# diodes.net
KiCad netlist of a schematic drawn in EAGLE
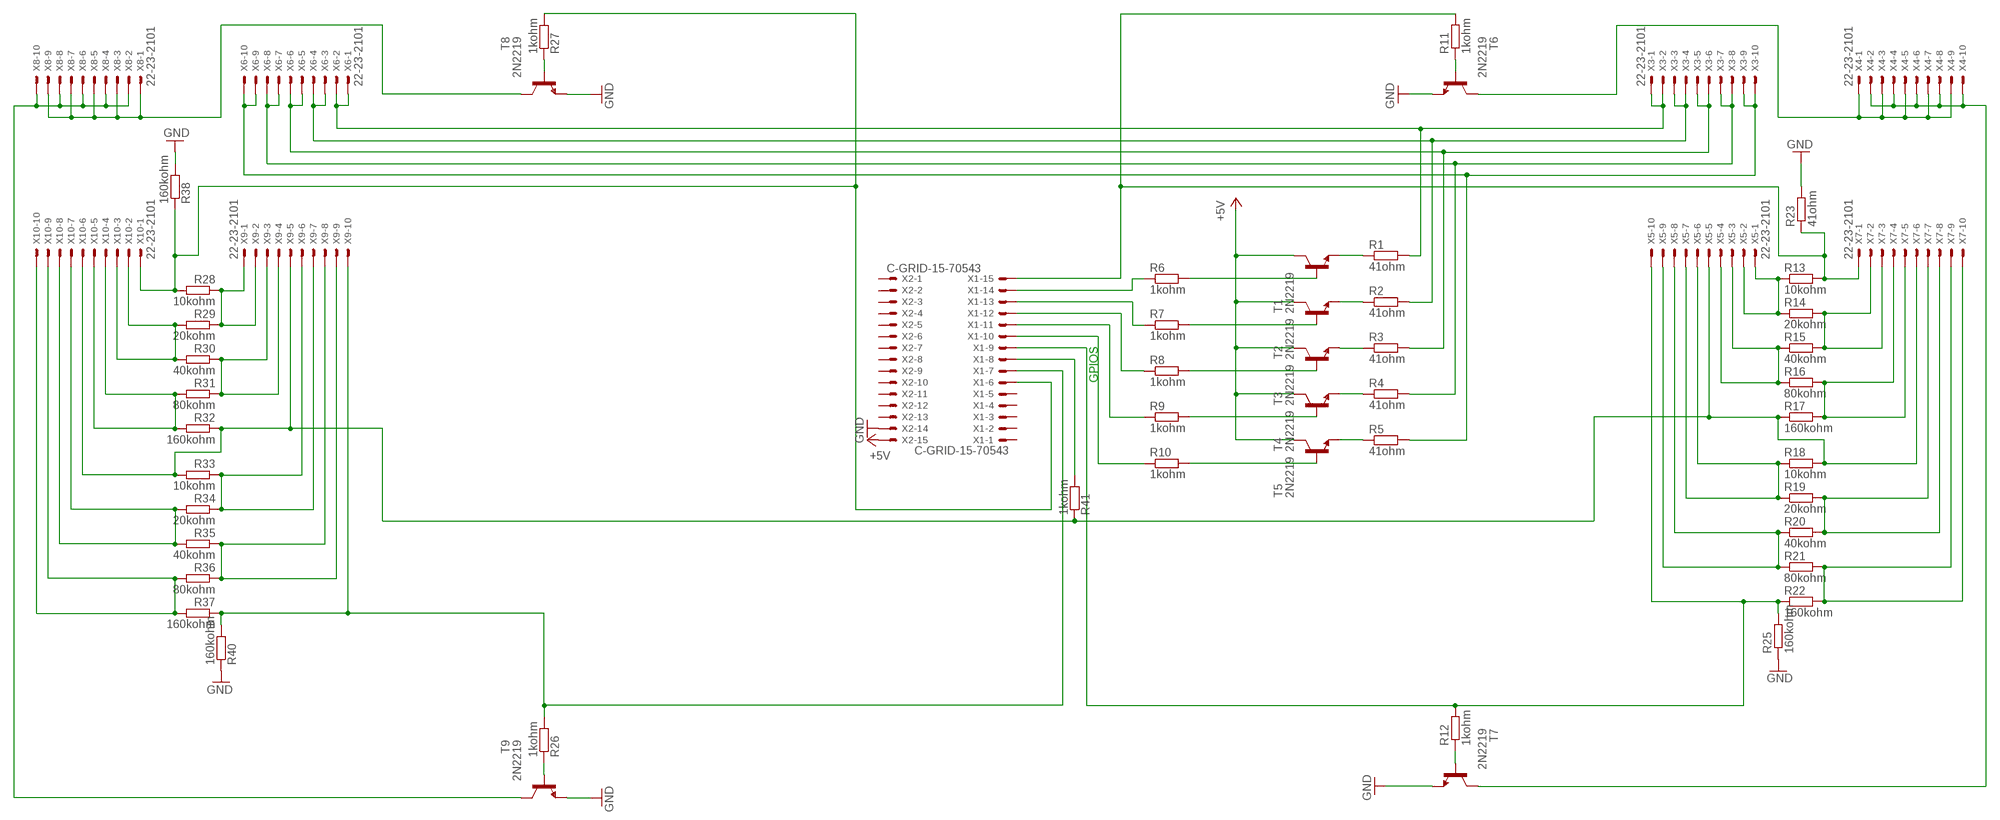
[diagram p0: schematic, sheet 1]

(export (version "E")
  (design (tool "Eeschema 10.0.6"))
  (components
    (comp (ref "R1")
      (value "41ohm")
      (footprint "eagle-import:0207_10")
      (libsource (lib "eagle-import") (part "R-EU_0207/10"))
    )
    (comp (ref "R2")
      (value "41ohm")
      (footprint "eagle-import:0207_10")
      (libsource (lib "eagle-import") (part "R-EU_0207/10"))
    )
    (comp (ref "R3")
      (value "41ohm")
      (footprint "eagle-import:0207_10")
      (libsource (lib "eagle-import") (part "R-EU_0207/10"))
    )
    (comp (ref "R4")
      (value "41ohm")
      (footprint "eagle-import:0207_10")
      (libsource (lib "eagle-import") (part "R-EU_0207/10"))
    )
    (comp (ref "R5")
      (value "41ohm")
      (footprint "eagle-import:0207_10")
      (libsource (lib "eagle-import") (part "R-EU_0207/10"))
    )
    (comp (ref "R6")
      (value "1kohm")
      (footprint "eagle-import:0207_10")
      (libsource (lib "eagle-import") (part "R-EU_0207/10"))
    )
    (comp (ref "R7")
      (value "1kohm")
      (footprint "eagle-import:0207_10")
      (libsource (lib "eagle-import") (part "R-EU_0207/10"))
    )
    (comp (ref "R8")
      (value "1kohm")
      (footprint "eagle-import:0207_10")
      (libsource (lib "eagle-import") (part "R-EU_0207/10"))
    )
    (comp (ref "R9")
      (value "1kohm")
      (footprint "eagle-import:0207_10")
      (libsource (lib "eagle-import") (part "R-EU_0207/10"))
    )
    (comp (ref "R10")
      (value "1kohm")
      (footprint "eagle-import:0207_10")
      (libsource (lib "eagle-import") (part "R-EU_0207/10"))
    )
    (comp (ref "R11")
      (value "1kohm")
      (footprint "eagle-import:0207_10")
      (libsource (lib "eagle-import") (part "R-EU_0207/10"))
    )
    (comp (ref "R12")
      (value "1kohm")
      (footprint "eagle-import:0207_10")
      (libsource (lib "eagle-import") (part "R-EU_0207/10"))
    )
    (comp (ref "R13")
      (value "10kohm")
      (footprint "eagle-import:0207_10")
      (libsource (lib "eagle-import") (part "R-EU_0207/10"))
    )
    (comp (ref "R14")
      (value "20kohm")
      (footprint "eagle-import:0207_10")
      (libsource (lib "eagle-import") (part "R-EU_0207/10"))
    )
    (comp (ref "R15")
      (value "40kohm")
      (footprint "eagle-import:0207_10")
      (libsource (lib "eagle-import") (part "R-EU_0207/10"))
    )
    (comp (ref "R16")
      (value "80kohm")
      (footprint "eagle-import:0207_10")
      (libsource (lib "eagle-import") (part "R-EU_0207/10"))
    )
    (comp (ref "R17")
      (value "160kohm")
      (footprint "eagle-import:0207_10")
      (libsource (lib "eagle-import") (part "R-EU_0207/10"))
    )
    (comp (ref "R18")
      (value "10kohm")
      (footprint "eagle-import:0207_10")
      (libsource (lib "eagle-import") (part "R-EU_0207/10"))
    )
    (comp (ref "R19")
      (value "20kohm")
      (footprint "eagle-import:0207_10")
      (libsource (lib "eagle-import") (part "R-EU_0207/10"))
    )
    (comp (ref "R20")
      (value "40kohm")
      (footprint "eagle-import:0207_10")
      (libsource (lib "eagle-import") (part "R-EU_0207/10"))
    )
    (comp (ref "R21")
      (value "80kohm")
      (footprint "eagle-import:0207_10")
      (libsource (lib "eagle-import") (part "R-EU_0207/10"))
    )
    (comp (ref "R22")
      (value "160kohm")
      (footprint "eagle-import:0207_10")
      (libsource (lib "eagle-import") (part "R-EU_0207/10"))
    )
    (comp (ref "R23")
      (value "41ohm")
      (footprint "eagle-import:0207_10")
      (libsource (lib "eagle-import") (part "R-EU_0207/10"))
    )
    (comp (ref "R25")
      (value "160kohm")
      (footprint "eagle-import:0207_10")
      (libsource (lib "eagle-import") (part "R-EU_0207/10"))
    )
    (comp (ref "R26")
      (value "1kohm")
      (footprint "eagle-import:0207_10")
      (libsource (lib "eagle-import") (part "R-EU_0207/10"))
    )
    (comp (ref "R27")
      (value "1kohm")
      (footprint "eagle-import:0207_10")
      (libsource (lib "eagle-import") (part "R-EU_0207/10"))
    )
    (comp (ref "R28")
      (value "10kohm")
      (footprint "eagle-import:0207_10")
      (libsource (lib "eagle-import") (part "R-EU_0207/10"))
    )
    (comp (ref "R29")
      (value "20kohm")
      (footprint "eagle-import:0207_10")
      (libsource (lib "eagle-import") (part "R-EU_0207/10"))
    )
    (comp (ref "R30")
      (value "40kohm")
      (footprint "eagle-import:0207_10")
      (libsource (lib "eagle-import") (part "R-EU_0207/10"))
    )
    (comp (ref "R31")
      (value "80kohm")
      (footprint "eagle-import:0207_10")
      (libsource (lib "eagle-import") (part "R-EU_0207/10"))
    )
    (comp (ref "R32")
      (value "160kohm")
      (footprint "eagle-import:0207_10")
      (libsource (lib "eagle-import") (part "R-EU_0207/10"))
    )
    (comp (ref "R33")
      (value "10kohm")
      (footprint "eagle-import:0207_10")
      (libsource (lib "eagle-import") (part "R-EU_0207/10"))
    )
    (comp (ref "R34")
      (value "20kohm")
      (footprint "eagle-import:0207_10")
      (libsource (lib "eagle-import") (part "R-EU_0207/10"))
    )
    (comp (ref "R35")
      (value "40kohm")
      (footprint "eagle-import:0207_10")
      (libsource (lib "eagle-import") (part "R-EU_0207/10"))
    )
    (comp (ref "R36")
      (value "80kohm")
      (footprint "eagle-import:0207_10")
      (libsource (lib "eagle-import") (part "R-EU_0207/10"))
    )
    (comp (ref "R37")
      (value "160kohm")
      (footprint "eagle-import:0207_10")
      (libsource (lib "eagle-import") (part "R-EU_0207/10"))
    )
    (comp (ref "R38")
      (value "160kohm")
      (footprint "eagle-import:0207_10")
      (libsource (lib "eagle-import") (part "R-EU_0207/10"))
    )
    (comp (ref "R40")
      (value "160kohm")
      (footprint "eagle-import:0207_10")
      (libsource (lib "eagle-import") (part "R-EU_0207/10"))
    )
    (comp (ref "R41")
      (value "1kohm")
      (footprint "eagle-import:0207_10")
      (libsource (lib "eagle-import") (part "R-EU_0207/10"))
    )
    (comp (ref "T1")
      (value "2N2219")
      (footprint "eagle-import:TO5")
      (libsource (lib "eagle-import") (part "2N2219"))
    )
    (comp (ref "T2")
      (value "2N2219")
      (footprint "eagle-import:TO5")
      (libsource (lib "eagle-import") (part "2N2219"))
    )
    (comp (ref "T3")
      (value "2N2219")
      (footprint "eagle-import:TO5")
      (libsource (lib "eagle-import") (part "2N2219"))
    )
    (comp (ref "T4")
      (value "2N2219")
      (footprint "eagle-import:TO5")
      (libsource (lib "eagle-import") (part "2N2219"))
    )
    (comp (ref "T5")
      (value "2N2219")
      (footprint "eagle-import:TO5")
      (libsource (lib "eagle-import") (part "2N2219"))
    )
    (comp (ref "T6")
      (value "2N2219")
      (footprint "eagle-import:TO5")
      (libsource (lib "eagle-import") (part "2N2219"))
    )
    (comp (ref "T7")
      (value "2N2219")
      (footprint "eagle-import:TO5")
      (libsource (lib "eagle-import") (part "2N2219"))
    )
    (comp (ref "T8")
      (value "2N2219")
      (footprint "eagle-import:TO5")
      (libsource (lib "eagle-import") (part "2N2219"))
    )
    (comp (ref "T9")
      (value "2N2219")
      (footprint "eagle-import:TO5")
      (libsource (lib "eagle-import") (part "2N2219"))
    )
    (comp (ref "X1")
      (value "C-GRID-15-70543")
      (footprint "eagle-import:70543-15")
      (fields (field (name "MF") "MOLEX"))
      (libsource (lib "eagle-import") (part "C-GRID-15-70543"))
    )
    (comp (ref "X2")
      (value "C-GRID-15-70543")
      (footprint "eagle-import:70543-15")
      (fields (field (name "MF") "MOLEX"))
      (libsource (lib "eagle-import") (part "C-GRID-15-70543"))
    )
    (comp (ref "X3")
      (value "22-23-2101")
      (footprint "eagle-import:22-23-2101")
      (fields (field (name "MF") "MOLEX"))
      (libsource (lib "eagle-import") (part "22-23-2101"))
    )
    (comp (ref "X4")
      (value "22-23-2101")
      (footprint "eagle-import:22-23-2101")
      (fields (field (name "MF") "MOLEX"))
      (libsource (lib "eagle-import") (part "22-23-2101"))
    )
    (comp (ref "X5")
      (value "22-23-2101")
      (footprint "eagle-import:22-23-2101")
      (fields (field (name "MF") "MOLEX"))
      (libsource (lib "eagle-import") (part "22-23-2101"))
    )
    (comp (ref "X6")
      (value "22-23-2101")
      (footprint "eagle-import:22-23-2101")
      (fields (field (name "MF") "MOLEX"))
      (libsource (lib "eagle-import") (part "22-23-2101"))
    )
    (comp (ref "X7")
      (value "22-23-2101")
      (footprint "eagle-import:22-23-2101")
      (fields (field (name "MF") "MOLEX"))
      (libsource (lib "eagle-import") (part "22-23-2101"))
    )
    (comp (ref "X8")
      (value "22-23-2101")
      (footprint "eagle-import:22-23-2101")
      (fields (field (name "MF") "MOLEX"))
      (libsource (lib "eagle-import") (part "22-23-2101"))
    )
    (comp (ref "X9")
      (value "22-23-2101")
      (footprint "eagle-import:22-23-2101")
      (fields (field (name "MF") "MOLEX"))
      (libsource (lib "eagle-import") (part "22-23-2101"))
    )
    (comp (ref "X10")
      (value "22-23-2101")
      (footprint "eagle-import:22-23-2101")
      (fields (field (name "MF") "MOLEX"))
      (libsource (lib "eagle-import") (part "22-23-2101"))
    )
  )
  (nets
    (net (code "1") (name "+5V") (class "Default")
      (node (ref "T1") (pin "3") (pinfunction "C_3") (pintype "passive"))
      (node (ref "T2") (pin "3") (pinfunction "C_3") (pintype "passive"))
      (node (ref "T3") (pin "3") (pinfunction "C_3") (pintype "passive"))
      (node (ref "T4") (pin "3") (pinfunction "C_3") (pintype "passive"))
      (node (ref "T5") (pin "3") (pinfunction "C_3") (pintype "passive"))
      (node (ref "X2") (pin "15") (pinfunction "S_15") (pintype "passive"))
    )
    (net (code "2") (name "GND") (class "Default")
      (node (ref "R23") (pin "2") (pinfunction "2_2") (pintype "passive"))
      (node (ref "R25") (pin "1") (pinfunction "1_1") (pintype "passive"))
      (node (ref "R38") (pin "2") (pinfunction "2_2") (pintype "passive"))
      (node (ref "R40") (pin "1") (pinfunction "1_1") (pintype "passive"))
      (node (ref "T6") (pin "1") (pinfunction "E_1") (pintype "passive"))
      (node (ref "T7") (pin "1") (pinfunction "E_1") (pintype "passive"))
      (node (ref "T8") (pin "1") (pinfunction "E_1") (pintype "passive"))
      (node (ref "T9") (pin "1") (pinfunction "E_1") (pintype "passive"))
      (node (ref "X2") (pin "14") (pinfunction "S_14") (pintype "passive"))
    )
    (net (code "3") (name "Net-(T1-B)") (class "Default")
      (node (ref "R6") (pin "2") (pinfunction "2_2") (pintype "passive"))
      (node (ref "T1") (pin "2") (pinfunction "B_2") (pintype "passive"))
    )
    (net (code "4") (name "Net-(T1-E)") (class "Default")
      (node (ref "R1") (pin "1") (pinfunction "1_1") (pintype "passive"))
      (node (ref "T1") (pin "1") (pinfunction "E_1") (pintype "passive"))
    )
    (net (code "5") (name "Net-(T2-B)") (class "Default")
      (node (ref "R7") (pin "2") (pinfunction "2_2") (pintype "passive"))
      (node (ref "T2") (pin "2") (pinfunction "B_2") (pintype "passive"))
    )
    (net (code "6") (name "Net-(T2-E)") (class "Default")
      (node (ref "R2") (pin "1") (pinfunction "1_1") (pintype "passive"))
      (node (ref "T2") (pin "1") (pinfunction "E_1") (pintype "passive"))
    )
    (net (code "7") (name "Net-(T3-B)") (class "Default")
      (node (ref "R8") (pin "2") (pinfunction "2_2") (pintype "passive"))
      (node (ref "T3") (pin "2") (pinfunction "B_2") (pintype "passive"))
    )
    (net (code "8") (name "Net-(T3-E)") (class "Default")
      (node (ref "R3") (pin "1") (pinfunction "1_1") (pintype "passive"))
      (node (ref "T3") (pin "1") (pinfunction "E_1") (pintype "passive"))
    )
    (net (code "9") (name "Net-(T4-B)") (class "Default")
      (node (ref "R9") (pin "2") (pinfunction "2_2") (pintype "passive"))
      (node (ref "T4") (pin "2") (pinfunction "B_2") (pintype "passive"))
    )
    (net (code "10") (name "Net-(T4-E)") (class "Default")
      (node (ref "R4") (pin "1") (pinfunction "1_1") (pintype "passive"))
      (node (ref "T4") (pin "1") (pinfunction "E_1") (pintype "passive"))
    )
    (net (code "11") (name "Net-(T5-B)") (class "Default")
      (node (ref "R10") (pin "2") (pinfunction "2_2") (pintype "passive"))
      (node (ref "T5") (pin "2") (pinfunction "B_2") (pintype "passive"))
    )
    (net (code "12") (name "Net-(T5-E)") (class "Default")
      (node (ref "R5") (pin "1") (pinfunction "1_1") (pintype "passive"))
      (node (ref "T5") (pin "1") (pinfunction "E_1") (pintype "passive"))
    )
    (net (code "13") (name "Net-(T6-B)") (class "Default")
      (node (ref "R11") (pin "1") (pinfunction "1_1") (pintype "passive"))
      (node (ref "T6") (pin "2") (pinfunction "B_2") (pintype "passive"))
    )
    (net (code "14") (name "Net-(T6-C)") (class "Default")
      (node (ref "T6") (pin "3") (pinfunction "C_3") (pintype "passive"))
      (node (ref "X4") (pin "1") (pinfunction "S_1") (pintype "passive"))
      (node (ref "X4") (pin "3") (pinfunction "S_3") (pintype "passive"))
      (node (ref "X4") (pin "5") (pinfunction "S_5") (pintype "passive"))
      (node (ref "X4") (pin "7") (pinfunction "S_7") (pintype "passive"))
      (node (ref "X4") (pin "9") (pinfunction "S_9") (pintype "passive"))
    )
    (net (code "15") (name "Net-(T7-B)") (class "Default")
      (node (ref "R12") (pin "1") (pinfunction "1_1") (pintype "passive"))
      (node (ref "T7") (pin "2") (pinfunction "B_2") (pintype "passive"))
    )
    (net (code "16") (name "Net-(T7-C)") (class "Default")
      (node (ref "T7") (pin "3") (pinfunction "C_3") (pintype "passive"))
      (node (ref "X4") (pin "10") (pinfunction "S_10") (pintype "passive"))
      (node (ref "X4") (pin "2") (pinfunction "S_2") (pintype "passive"))
      (node (ref "X4") (pin "4") (pinfunction "S_4") (pintype "passive"))
      (node (ref "X4") (pin "6") (pinfunction "S_6") (pintype "passive"))
      (node (ref "X4") (pin "8") (pinfunction "S_8") (pintype "passive"))
    )
    (net (code "17") (name "Net-(T8-B)") (class "Default")
      (node (ref "R27") (pin "1") (pinfunction "1_1") (pintype "passive"))
      (node (ref "T8") (pin "2") (pinfunction "B_2") (pintype "passive"))
    )
    (net (code "18") (name "Net-(T8-C)") (class "Default")
      (node (ref "T8") (pin "3") (pinfunction "C_3") (pintype "passive"))
      (node (ref "X8") (pin "1") (pinfunction "S_1") (pintype "passive"))
      (node (ref "X8") (pin "3") (pinfunction "S_3") (pintype "passive"))
      (node (ref "X8") (pin "5") (pinfunction "S_5") (pintype "passive"))
      (node (ref "X8") (pin "7") (pinfunction "S_7") (pintype "passive"))
      (node (ref "X8") (pin "9") (pinfunction "S_9") (pintype "passive"))
    )
    (net (code "19") (name "Net-(T9-B)") (class "Default")
      (node (ref "R26") (pin "1") (pinfunction "1_1") (pintype "passive"))
      (node (ref "T9") (pin "2") (pinfunction "B_2") (pintype "passive"))
    )
    (net (code "20") (name "Net-(T9-C)") (class "Default")
      (node (ref "T9") (pin "3") (pinfunction "C_3") (pintype "passive"))
      (node (ref "X8") (pin "10") (pinfunction "S_10") (pintype "passive"))
      (node (ref "X8") (pin "2") (pinfunction "S_2") (pintype "passive"))
      (node (ref "X8") (pin "4") (pinfunction "S_4") (pintype "passive"))
      (node (ref "X8") (pin "6") (pinfunction "S_6") (pintype "passive"))
      (node (ref "X8") (pin "8") (pinfunction "S_8") (pintype "passive"))
    )
    (net (code "21") (name "Net-(X1B-S)") (class "Default")
      (node (ref "R10") (pin "1") (pinfunction "1_1") (pintype "passive"))
      (node (ref "X1") (pin "10") (pinfunction "S_10") (pintype "passive"))
    )
    (net (code "22") (name "Net-(X1C-S)") (class "Default")
      (node (ref "R9") (pin "1") (pinfunction "1_1") (pintype "passive"))
      (node (ref "X1") (pin "11") (pinfunction "S_11") (pintype "passive"))
    )
    (net (code "23") (name "Net-(X1D-S)") (class "Default")
      (node (ref "R8") (pin "1") (pinfunction "1_1") (pintype "passive"))
      (node (ref "X1") (pin "12") (pinfunction "S_12") (pintype "passive"))
    )
    (net (code "24") (name "Net-(X1E-S)") (class "Default")
      (node (ref "R7") (pin "1") (pinfunction "1_1") (pintype "passive"))
      (node (ref "X1") (pin "13") (pinfunction "S_13") (pintype "passive"))
    )
    (net (code "25") (name "Net-(X1F-S)") (class "Default")
      (node (ref "R6") (pin "1") (pinfunction "1_1") (pintype "passive"))
      (node (ref "X1") (pin "14") (pinfunction "S_14") (pintype "passive"))
    )
    (net (code "26") (name "Net-(X1G-S)") (class "Default")
      (node (ref "R11") (pin "2") (pinfunction "2_2") (pintype "passive"))
      (node (ref "R13") (pin "2") (pinfunction "2_2") (pintype "passive"))
      (node (ref "R23") (pin "1") (pinfunction "1_1") (pintype "passive"))
      (node (ref "X1") (pin "15") (pinfunction "S_15") (pintype "passive"))
      (node (ref "X7") (pin "1") (pinfunction "S_1") (pintype "passive"))
    )
    (net (code "27") (name "Net-(X1M-S)") (class "Default")
      (node (ref "R26") (pin "2") (pinfunction "2_2") (pintype "passive"))
      (node (ref "R37") (pin "1") (pinfunction "1_1") (pintype "passive"))
      (node (ref "R40") (pin "2") (pinfunction "2_2") (pintype "passive"))
      (node (ref "X1") (pin "7") (pinfunction "S_7") (pintype "passive"))
      (node (ref "X9") (pin "10") (pinfunction "S_10") (pintype "passive"))
    )
    (net (code "28") (name "Net-(X1N-S)") (class "Default")
      (node (ref "R41") (pin "2") (pinfunction "2_2") (pintype "passive"))
      (node (ref "X1") (pin "8") (pinfunction "S_8") (pintype "passive"))
    )
    (net (code "29") (name "Net-(X1O-S)") (class "Default")
      (node (ref "R12") (pin "2") (pinfunction "2_2") (pintype "passive"))
      (node (ref "R22") (pin "1") (pinfunction "1_1") (pintype "passive"))
      (node (ref "R25") (pin "2") (pinfunction "2_2") (pintype "passive"))
      (node (ref "X1") (pin "9") (pinfunction "S_9") (pintype "passive"))
      (node (ref "X5") (pin "10") (pinfunction "S_10") (pintype "passive"))
    )
    (net (code "30") (name "Net-(X3A-S)") (class "Default")
      (node (ref "R1") (pin "2") (pinfunction "2_2") (pintype "passive"))
      (node (ref "X3") (pin "1") (pinfunction "S_1") (pintype "passive"))
      (node (ref "X3") (pin "2") (pinfunction "S_2") (pintype "passive"))
      (node (ref "X6") (pin "1") (pinfunction "S_1") (pintype "passive"))
      (node (ref "X6") (pin "2") (pinfunction "S_2") (pintype "passive"))
    )
    (net (code "31") (name "Net-(X3B-S)") (class "Default")
      (node (ref "R5") (pin "2") (pinfunction "2_2") (pintype "passive"))
      (node (ref "X3") (pin "10") (pinfunction "S_10") (pintype "passive"))
      (node (ref "X3") (pin "9") (pinfunction "S_9") (pintype "passive"))
      (node (ref "X6") (pin "10") (pinfunction "S_10") (pintype "passive"))
      (node (ref "X6") (pin "9") (pinfunction "S_9") (pintype "passive"))
    )
    (net (code "32") (name "Net-(X3D-S)") (class "Default")
      (node (ref "R2") (pin "2") (pinfunction "2_2") (pintype "passive"))
      (node (ref "X3") (pin "3") (pinfunction "S_3") (pintype "passive"))
      (node (ref "X3") (pin "4") (pinfunction "S_4") (pintype "passive"))
      (node (ref "X6") (pin "3") (pinfunction "S_3") (pintype "passive"))
      (node (ref "X6") (pin "4") (pinfunction "S_4") (pintype "passive"))
    )
    (net (code "33") (name "Net-(X3F-S)") (class "Default")
      (node (ref "R3") (pin "2") (pinfunction "2_2") (pintype "passive"))
      (node (ref "X3") (pin "5") (pinfunction "S_5") (pintype "passive"))
      (node (ref "X3") (pin "6") (pinfunction "S_6") (pintype "passive"))
      (node (ref "X6") (pin "5") (pinfunction "S_5") (pintype "passive"))
      (node (ref "X6") (pin "6") (pinfunction "S_6") (pintype "passive"))
    )
    (net (code "34") (name "Net-(X3H-S)") (class "Default")
      (node (ref "R4") (pin "2") (pinfunction "2_2") (pintype "passive"))
      (node (ref "X3") (pin "7") (pinfunction "S_7") (pintype "passive"))
      (node (ref "X3") (pin "8") (pinfunction "S_8") (pintype "passive"))
      (node (ref "X6") (pin "7") (pinfunction "S_7") (pintype "passive"))
      (node (ref "X6") (pin "8") (pinfunction "S_8") (pintype "passive"))
    )
    (net (code "35") (name "Net-(X5A-S)") (class "Default")
      (node (ref "R13") (pin "1") (pinfunction "1_1") (pintype "passive"))
      (node (ref "R14") (pin "1") (pinfunction "1_1") (pintype "passive"))
      (node (ref "X5") (pin "1") (pinfunction "S_1") (pintype "passive"))
      (node (ref "X5") (pin "2") (pinfunction "S_2") (pintype "passive"))
    )
    (net (code "36") (name "Net-(X5D-S)") (class "Default")
      (node (ref "R15") (pin "1") (pinfunction "1_1") (pintype "passive"))
      (node (ref "R16") (pin "1") (pinfunction "1_1") (pintype "passive"))
      (node (ref "X5") (pin "3") (pinfunction "S_3") (pintype "passive"))
      (node (ref "X5") (pin "4") (pinfunction "S_4") (pintype "passive"))
    )
    (net (code "37") (name "Net-(X5G-S)") (class "Default")
      (node (ref "R18") (pin "1") (pinfunction "1_1") (pintype "passive"))
      (node (ref "R19") (pin "1") (pinfunction "1_1") (pintype "passive"))
      (node (ref "X5") (pin "6") (pinfunction "S_6") (pintype "passive"))
      (node (ref "X5") (pin "7") (pinfunction "S_7") (pintype "passive"))
    )
    (net (code "38") (name "Net-(X5I-S)") (class "Default")
      (node (ref "R20") (pin "1") (pinfunction "1_1") (pintype "passive"))
      (node (ref "R21") (pin "1") (pinfunction "1_1") (pintype "passive"))
      (node (ref "X5") (pin "8") (pinfunction "S_8") (pintype "passive"))
      (node (ref "X5") (pin "9") (pinfunction "S_9") (pintype "passive"))
    )
    (net (code "39") (name "Net-(X7B-S)") (class "Default")
      (node (ref "R21") (pin "2") (pinfunction "2_2") (pintype "passive"))
      (node (ref "R22") (pin "2") (pinfunction "2_2") (pintype "passive"))
      (node (ref "X7") (pin "10") (pinfunction "S_10") (pintype "passive"))
      (node (ref "X7") (pin "9") (pinfunction "S_9") (pintype "passive"))
    )
    (net (code "40") (name "Net-(X7C-S)") (class "Default")
      (node (ref "R14") (pin "2") (pinfunction "2_2") (pintype "passive"))
      (node (ref "R15") (pin "2") (pinfunction "2_2") (pintype "passive"))
      (node (ref "X7") (pin "2") (pinfunction "S_2") (pintype "passive"))
      (node (ref "X7") (pin "3") (pinfunction "S_3") (pintype "passive"))
    )
    (net (code "41") (name "Net-(X7E-S)") (class "Default")
      (node (ref "R16") (pin "2") (pinfunction "2_2") (pintype "passive"))
      (node (ref "R17") (pin "2") (pinfunction "2_2") (pintype "passive"))
      (node (ref "X7") (pin "4") (pinfunction "S_4") (pintype "passive"))
      (node (ref "X7") (pin "5") (pinfunction "S_5") (pintype "passive"))
    )
    (net (code "42") (name "Net-(X7H-S)") (class "Default")
      (node (ref "R19") (pin "2") (pinfunction "2_2") (pintype "passive"))
      (node (ref "R20") (pin "2") (pinfunction "2_2") (pintype "passive"))
      (node (ref "X7") (pin "7") (pinfunction "S_7") (pintype "passive"))
      (node (ref "X7") (pin "8") (pinfunction "S_8") (pintype "passive"))
    )
    (net (code "43") (name "Net-(X9A-S)") (class "Default")
      (node (ref "R28") (pin "1") (pinfunction "1_1") (pintype "passive"))
      (node (ref "R29") (pin "1") (pinfunction "1_1") (pintype "passive"))
      (node (ref "X9") (pin "1") (pinfunction "S_1") (pintype "passive"))
      (node (ref "X9") (pin "2") (pinfunction "S_2") (pintype "passive"))
    )
    (net (code "44") (name "Net-(X9D-S)") (class "Default")
      (node (ref "R30") (pin "1") (pinfunction "1_1") (pintype "passive"))
      (node (ref "R31") (pin "1") (pinfunction "1_1") (pintype "passive"))
      (node (ref "X9") (pin "3") (pinfunction "S_3") (pintype "passive"))
      (node (ref "X9") (pin "4") (pinfunction "S_4") (pintype "passive"))
    )
    (net (code "45") (name "Net-(X9G-S)") (class "Default")
      (node (ref "R33") (pin "1") (pinfunction "1_1") (pintype "passive"))
      (node (ref "R34") (pin "1") (pinfunction "1_1") (pintype "passive"))
      (node (ref "X9") (pin "6") (pinfunction "S_6") (pintype "passive"))
      (node (ref "X9") (pin "7") (pinfunction "S_7") (pintype "passive"))
    )
    (net (code "46") (name "Net-(X9I-S)") (class "Default")
      (node (ref "R35") (pin "1") (pinfunction "1_1") (pintype "passive"))
      (node (ref "R36") (pin "1") (pinfunction "1_1") (pintype "passive"))
      (node (ref "X9") (pin "8") (pinfunction "S_8") (pintype "passive"))
      (node (ref "X9") (pin "9") (pinfunction "S_9") (pintype "passive"))
    )
    (net (code "47") (name "Net-(X10A-S)") (class "Default")
      (node (ref "R27") (pin "2") (pinfunction "2_2") (pintype "passive"))
      (node (ref "R28") (pin "2") (pinfunction "2_2") (pintype "passive"))
      (node (ref "R38") (pin "1") (pinfunction "1_1") (pintype "passive"))
      (node (ref "X1") (pin "6") (pinfunction "S_6") (pintype "passive"))
      (node (ref "X10") (pin "1") (pinfunction "S_1") (pintype "passive"))
    )
    (net (code "48") (name "Net-(X10B-S)") (class "Default")
      (node (ref "R36") (pin "2") (pinfunction "2_2") (pintype "passive"))
      (node (ref "R37") (pin "2") (pinfunction "2_2") (pintype "passive"))
      (node (ref "X10") (pin "10") (pinfunction "S_10") (pintype "passive"))
      (node (ref "X10") (pin "9") (pinfunction "S_9") (pintype "passive"))
    )
    (net (code "49") (name "Net-(X10C-S)") (class "Default")
      (node (ref "R29") (pin "2") (pinfunction "2_2") (pintype "passive"))
      (node (ref "R30") (pin "2") (pinfunction "2_2") (pintype "passive"))
      (node (ref "X10") (pin "2") (pinfunction "S_2") (pintype "passive"))
      (node (ref "X10") (pin "3") (pinfunction "S_3") (pintype "passive"))
    )
    (net (code "50") (name "Net-(X10E-S)") (class "Default")
      (node (ref "R31") (pin "2") (pinfunction "2_2") (pintype "passive"))
      (node (ref "R32") (pin "2") (pinfunction "2_2") (pintype "passive"))
      (node (ref "X10") (pin "4") (pinfunction "S_4") (pintype "passive"))
      (node (ref "X10") (pin "5") (pinfunction "S_5") (pintype "passive"))
    )
    (net (code "51") (name "Net-(X10G-S)") (class "Default")
      (node (ref "R17") (pin "1") (pinfunction "1_1") (pintype "passive"))
      (node (ref "R18") (pin "2") (pinfunction "2_2") (pintype "passive"))
      (node (ref "R32") (pin "1") (pinfunction "1_1") (pintype "passive"))
      (node (ref "R33") (pin "2") (pinfunction "2_2") (pintype "passive"))
      (node (ref "R41") (pin "1") (pinfunction "1_1") (pintype "passive"))
      (node (ref "X10") (pin "6") (pinfunction "S_6") (pintype "passive"))
      (node (ref "X5") (pin "5") (pinfunction "S_5") (pintype "passive"))
      (node (ref "X7") (pin "6") (pinfunction "S_6") (pintype "passive"))
      (node (ref "X9") (pin "5") (pinfunction "S_5") (pintype "passive"))
    )
    (net (code "52") (name "Net-(X10H-S)") (class "Default")
      (node (ref "R34") (pin "2") (pinfunction "2_2") (pintype "passive"))
      (node (ref "R35") (pin "2") (pinfunction "2_2") (pintype "passive"))
      (node (ref "X10") (pin "7") (pinfunction "S_7") (pintype "passive"))
      (node (ref "X10") (pin "8") (pinfunction "S_8") (pintype "passive"))
    )
    (net (code "53") (name "unconnected-(X1A-S-Pad1)") (class "Default")
      (node (ref "X1") (pin "1") (pinfunction "S_1") (pintype "passive"))
    )
    (net (code "54") (name "unconnected-(X1H-S-Pad2)") (class "Default")
      (node (ref "X1") (pin "2") (pinfunction "S_2") (pintype "passive"))
    )
    (net (code "55") (name "unconnected-(X1I-S-Pad3)") (class "Default")
      (node (ref "X1") (pin "3") (pinfunction "S_3") (pintype "passive"))
    )
    (net (code "56") (name "unconnected-(X1J-S-Pad4)") (class "Default")
      (node (ref "X1") (pin "4") (pinfunction "S_4") (pintype "passive"))
    )
    (net (code "57") (name "unconnected-(X1K-S-Pad5)") (class "Default")
      (node (ref "X1") (pin "5") (pinfunction "S_5") (pintype "passive"))
    )
    (net (code "58") (name "unconnected-(X2A-S-Pad1)") (class "Default")
      (node (ref "X2") (pin "1") (pinfunction "S_1") (pintype "passive"))
    )
    (net (code "59") (name "unconnected-(X2B-S-Pad10)") (class "Default")
      (node (ref "X2") (pin "10") (pinfunction "S_10") (pintype "passive"))
    )
    (net (code "60") (name "unconnected-(X2C-S-Pad11)") (class "Default")
      (node (ref "X2") (pin "11") (pinfunction "S_11") (pintype "passive"))
    )
    (net (code "61") (name "unconnected-(X2D-S-Pad12)") (class "Default")
      (node (ref "X2") (pin "12") (pinfunction "S_12") (pintype "passive"))
    )
    (net (code "62") (name "unconnected-(X2E-S-Pad13)") (class "Default")
      (node (ref "X2") (pin "13") (pinfunction "S_13") (pintype "passive"))
    )
    (net (code "63") (name "unconnected-(X2H-S-Pad2)") (class "Default")
      (node (ref "X2") (pin "2") (pinfunction "S_2") (pintype "passive"))
    )
    (net (code "64") (name "unconnected-(X2I-S-Pad3)") (class "Default")
      (node (ref "X2") (pin "3") (pinfunction "S_3") (pintype "passive"))
    )
    (net (code "65") (name "unconnected-(X2J-S-Pad4)") (class "Default")
      (node (ref "X2") (pin "4") (pinfunction "S_4") (pintype "passive"))
    )
    (net (code "66") (name "unconnected-(X2K-S-Pad5)") (class "Default")
      (node (ref "X2") (pin "5") (pinfunction "S_5") (pintype "passive"))
    )
    (net (code "67") (name "unconnected-(X2L-S-Pad6)") (class "Default")
      (node (ref "X2") (pin "6") (pinfunction "S_6") (pintype "passive"))
    )
    (net (code "68") (name "unconnected-(X2M-S-Pad7)") (class "Default")
      (node (ref "X2") (pin "7") (pinfunction "S_7") (pintype "passive"))
    )
    (net (code "69") (name "unconnected-(X2N-S-Pad8)") (class "Default")
      (node (ref "X2") (pin "8") (pinfunction "S_8") (pintype "passive"))
    )
    (net (code "70") (name "unconnected-(X2O-S-Pad9)") (class "Default")
      (node (ref "X2") (pin "9") (pinfunction "S_9") (pintype "passive"))
    )
  )
)
